# schaltplan.net
KiCad netlist of a schematic drawn in EAGLE
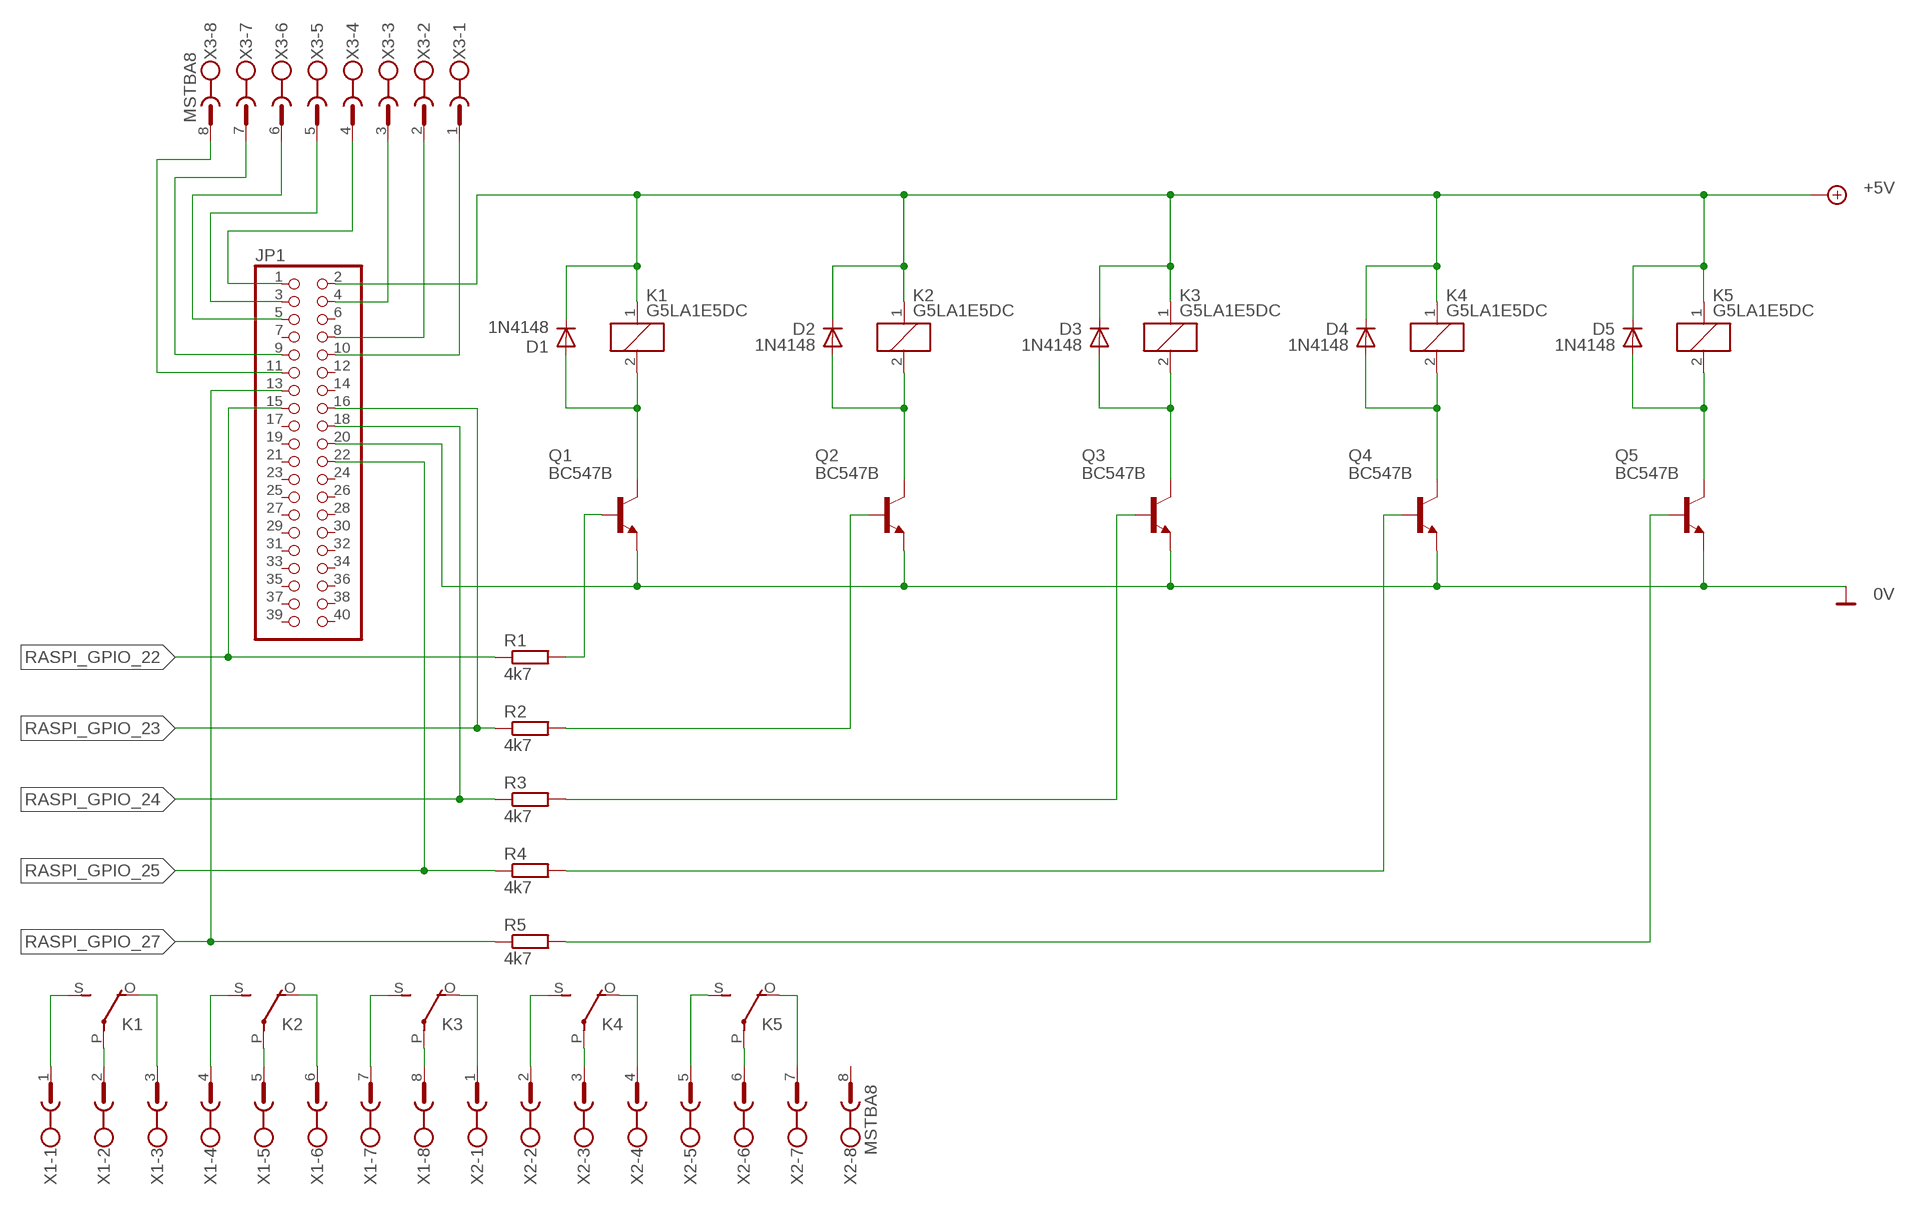
[diagram p0: schematic, sheet 1]

(export (version "E")
  (design (tool "Eeschema 10.0.6"))
  (components
    (comp (ref "D1")
      (value "1N4148")
      (footprint "eagle-import:DO35-10")
      (libsource (lib "eagle-import") (part "1N4148DO35-10"))
    )
    (comp (ref "D2")
      (value "1N4148")
      (footprint "eagle-import:DO35-10")
      (libsource (lib "eagle-import") (part "1N4148DO35-10"))
    )
    (comp (ref "D3")
      (value "1N4148")
      (footprint "eagle-import:DO35-10")
      (libsource (lib "eagle-import") (part "1N4148DO35-10"))
    )
    (comp (ref "D4")
      (value "1N4148")
      (footprint "eagle-import:DO35-10")
      (libsource (lib "eagle-import") (part "1N4148DO35-10"))
    )
    (comp (ref "D5")
      (value "1N4148")
      (footprint "eagle-import:DO35-10")
      (libsource (lib "eagle-import") (part "1N4148DO35-10"))
    )
    (comp (ref "JP1")
      (value "PINHD-2X20")
      (footprint "eagle-import:2X20")
      (libsource (lib "eagle-import") (part "PINHD-2X20"))
    )
    (comp (ref "K1")
      (value "G5LA1E5DC")
      (footprint "eagle-import:G5LE")
      (libsource (lib "eagle-import") (part "G5L"))
    )
    (comp (ref "K2")
      (value "G5LA1E5DC")
      (footprint "eagle-import:G5LE")
      (libsource (lib "eagle-import") (part "G5L"))
    )
    (comp (ref "K3")
      (value "G5LA1E5DC")
      (footprint "eagle-import:G5LE")
      (libsource (lib "eagle-import") (part "G5L"))
    )
    (comp (ref "K4")
      (value "G5LA1E5DC")
      (footprint "eagle-import:G5LE")
      (libsource (lib "eagle-import") (part "G5L"))
    )
    (comp (ref "K5")
      (value "G5LA1E5DC")
      (footprint "eagle-import:G5LE")
      (libsource (lib "eagle-import") (part "G5L"))
    )
    (comp (ref "Q1")
      (value "BC547B")
      (footprint "eagle-import:TO92")
      (libsource (lib "eagle-import") (part "BC547B"))
    )
    (comp (ref "Q2")
      (value "BC547B")
      (footprint "eagle-import:TO92")
      (libsource (lib "eagle-import") (part "BC547B"))
    )
    (comp (ref "Q3")
      (value "BC547B")
      (footprint "eagle-import:TO92")
      (libsource (lib "eagle-import") (part "BC547B"))
    )
    (comp (ref "Q4")
      (value "BC547B")
      (footprint "eagle-import:TO92")
      (libsource (lib "eagle-import") (part "BC547B"))
    )
    (comp (ref "Q5")
      (value "BC547B")
      (footprint "eagle-import:TO92")
      (libsource (lib "eagle-import") (part "BC547B"))
    )
    (comp (ref "R1")
      (value "4k7")
      (footprint "eagle-import:0207_10")
      (libsource (lib "eagle-import") (part "R-EU_0207/10"))
    )
    (comp (ref "R2")
      (value "4k7")
      (footprint "eagle-import:0207_10")
      (libsource (lib "eagle-import") (part "R-EU_0207/10"))
    )
    (comp (ref "R3")
      (value "4k7")
      (footprint "eagle-import:0207_10")
      (libsource (lib "eagle-import") (part "R-EU_0207/10"))
    )
    (comp (ref "R4")
      (value "4k7")
      (footprint "eagle-import:0207_10")
      (libsource (lib "eagle-import") (part "R-EU_0207/10"))
    )
    (comp (ref "R5")
      (value "4k7")
      (footprint "eagle-import:0207_10")
      (libsource (lib "eagle-import") (part "R-EU_0207/10"))
    )
    (comp (ref "X1")
      (value "MSTBA8")
      (footprint "eagle-import:MSTBA8")
      (fields (field (name "MF") "FARNELL") (field (name "MPN") "1757307"))
      (libsource (lib "eagle-import") (part "MSTBA8"))
    )
    (comp (ref "X2")
      (value "MSTBA8")
      (footprint "eagle-import:MSTBA8")
      (fields (field (name "MF") "FARNELL") (field (name "MPN") "1757307"))
      (libsource (lib "eagle-import") (part "MSTBA8"))
    )
    (comp (ref "X3")
      (value "MSTBA8")
      (footprint "eagle-import:MSTBA8")
      (fields (field (name "MF") "FARNELL") (field (name "MPN") "1757307"))
      (libsource (lib "eagle-import") (part "MSTBA8"))
    )
  )
  (nets
    (net (code "1") (name "+5V") (class "Default")
      (node (ref "D1") (pin "C") (pinfunction "C_C") (pintype "passive"))
      (node (ref "D2") (pin "C") (pinfunction "C_C") (pintype "passive"))
      (node (ref "D3") (pin "C") (pinfunction "C_C") (pintype "passive"))
      (node (ref "D4") (pin "C") (pinfunction "C_C") (pintype "passive"))
      (node (ref "D5") (pin "C") (pinfunction "C_C") (pintype "passive"))
      (node (ref "JP1") (pin "2") (pinfunction "2_2") (pintype "passive"))
      (node (ref "K1") (pin "1") (pinfunction "1_1") (pintype "passive"))
      (node (ref "K2") (pin "1") (pinfunction "1_1") (pintype "passive"))
      (node (ref "K3") (pin "1") (pinfunction "1_1") (pintype "passive"))
      (node (ref "K4") (pin "1") (pinfunction "1_1") (pintype "passive"))
      (node (ref "K5") (pin "1") (pinfunction "1_1") (pintype "passive"))
    )
    (net (code "2") (name "0V") (class "Default")
      (node (ref "JP1") (pin "20") (pinfunction "20_20") (pintype "passive"))
      (node (ref "Q1") (pin "1") (pinfunction "E_1") (pintype "passive"))
      (node (ref "Q2") (pin "1") (pinfunction "E_1") (pintype "passive"))
      (node (ref "Q3") (pin "1") (pinfunction "E_1") (pintype "passive"))
      (node (ref "Q4") (pin "1") (pinfunction "E_1") (pintype "passive"))
      (node (ref "Q5") (pin "1") (pinfunction "E_1") (pintype "passive"))
    )
    (net (code "3") (name "Net-(JP1-Pad10)") (class "Default")
      (node (ref "JP1") (pin "10") (pinfunction "10_10") (pintype "passive"))
      (node (ref "X3") (pin "1") (pinfunction "1_1") (pintype "passive"))
    )
    (net (code "4") (name "Net-(K1-PadS)") (class "Default")
      (node (ref "K1") (pin "S") (pinfunction "S_S") (pintype "passive"))
      (node (ref "X1") (pin "1") (pinfunction "1_1") (pintype "passive"))
    )
    (net (code "5") (name "Net-(K3-PadO)") (class "Default")
      (node (ref "K3") (pin "O") (pinfunction "O_O") (pintype "passive"))
      (node (ref "X2") (pin "1") (pinfunction "1_1") (pintype "passive"))
    )
    (net (code "6") (name "Net-(Q1-B)") (class "Default")
      (node (ref "Q1") (pin "2") (pinfunction "B_2") (pintype "passive"))
      (node (ref "R1") (pin "2") (pinfunction "2_2") (pintype "passive"))
    )
    (net (code "7") (name "Net-(Q1-C)") (class "Default")
      (node (ref "D1") (pin "A") (pinfunction "A_A") (pintype "passive"))
      (node (ref "K1") (pin "2") (pinfunction "2_2") (pintype "passive"))
      (node (ref "Q1") (pin "3") (pinfunction "C_3") (pintype "passive"))
    )
    (net (code "8") (name "Net-(Q2-B)") (class "Default")
      (node (ref "Q2") (pin "2") (pinfunction "B_2") (pintype "passive"))
      (node (ref "R2") (pin "2") (pinfunction "2_2") (pintype "passive"))
    )
    (net (code "9") (name "Net-(Q2-C)") (class "Default")
      (node (ref "D2") (pin "A") (pinfunction "A_A") (pintype "passive"))
      (node (ref "K2") (pin "2") (pinfunction "2_2") (pintype "passive"))
      (node (ref "Q2") (pin "3") (pinfunction "C_3") (pintype "passive"))
    )
    (net (code "10") (name "Net-(Q3-B)") (class "Default")
      (node (ref "Q3") (pin "2") (pinfunction "B_2") (pintype "passive"))
      (node (ref "R3") (pin "2") (pinfunction "2_2") (pintype "passive"))
    )
    (net (code "11") (name "Net-(Q3-C)") (class "Default")
      (node (ref "D3") (pin "A") (pinfunction "A_A") (pintype "passive"))
      (node (ref "K3") (pin "2") (pinfunction "2_2") (pintype "passive"))
      (node (ref "Q3") (pin "3") (pinfunction "C_3") (pintype "passive"))
    )
    (net (code "12") (name "Net-(Q4-B)") (class "Default")
      (node (ref "Q4") (pin "2") (pinfunction "B_2") (pintype "passive"))
      (node (ref "R4") (pin "2") (pinfunction "2_2") (pintype "passive"))
    )
    (net (code "13") (name "Net-(Q4-C)") (class "Default")
      (node (ref "D4") (pin "A") (pinfunction "A_A") (pintype "passive"))
      (node (ref "K4") (pin "2") (pinfunction "2_2") (pintype "passive"))
      (node (ref "Q4") (pin "3") (pinfunction "C_3") (pintype "passive"))
    )
    (net (code "14") (name "Net-(Q5-B)") (class "Default")
      (node (ref "Q5") (pin "2") (pinfunction "B_2") (pintype "passive"))
      (node (ref "R5") (pin "2") (pinfunction "2_2") (pintype "passive"))
    )
    (net (code "15") (name "Net-(Q5-C)") (class "Default")
      (node (ref "D5") (pin "A") (pinfunction "A_A") (pintype "passive"))
      (node (ref "K5") (pin "2") (pinfunction "2_2") (pintype "passive"))
      (node (ref "Q5") (pin "3") (pinfunction "C_3") (pintype "passive"))
    )
    (net (code "16") (name "Net-(X1B-1)") (class "Default")
      (node (ref "K1") (pin "P") (pinfunction "P_P") (pintype "passive"))
      (node (ref "X1") (pin "2") (pinfunction "1_2") (pintype "passive"))
    )
    (net (code "17") (name "Net-(X1C-1)") (class "Default")
      (node (ref "K1") (pin "O") (pinfunction "O_O") (pintype "passive"))
      (node (ref "X1") (pin "3") (pinfunction "1_3") (pintype "passive"))
    )
    (net (code "18") (name "Net-(X1D-1)") (class "Default")
      (node (ref "K2") (pin "S") (pinfunction "S_S") (pintype "passive"))
      (node (ref "X1") (pin "4") (pinfunction "1_4") (pintype "passive"))
    )
    (net (code "19") (name "Net-(X1E-1)") (class "Default")
      (node (ref "K2") (pin "P") (pinfunction "P_P") (pintype "passive"))
      (node (ref "X1") (pin "5") (pinfunction "1_5") (pintype "passive"))
    )
    (net (code "20") (name "Net-(X1F-1)") (class "Default")
      (node (ref "K2") (pin "O") (pinfunction "O_O") (pintype "passive"))
      (node (ref "X1") (pin "6") (pinfunction "1_6") (pintype "passive"))
    )
    (net (code "21") (name "Net-(X1G-1)") (class "Default")
      (node (ref "K3") (pin "S") (pinfunction "S_S") (pintype "passive"))
      (node (ref "X1") (pin "7") (pinfunction "1_7") (pintype "passive"))
    )
    (net (code "22") (name "Net-(X1H-1)") (class "Default")
      (node (ref "K3") (pin "P") (pinfunction "P_P") (pintype "passive"))
      (node (ref "X1") (pin "8") (pinfunction "1_8") (pintype "passive"))
    )
    (net (code "23") (name "Net-(X2B-1)") (class "Default")
      (node (ref "K4") (pin "S") (pinfunction "S_S") (pintype "passive"))
      (node (ref "X2") (pin "2") (pinfunction "1_2") (pintype "passive"))
    )
    (net (code "24") (name "Net-(X2C-1)") (class "Default")
      (node (ref "K4") (pin "P") (pinfunction "P_P") (pintype "passive"))
      (node (ref "X2") (pin "3") (pinfunction "1_3") (pintype "passive"))
    )
    (net (code "25") (name "Net-(X2D-1)") (class "Default")
      (node (ref "K4") (pin "O") (pinfunction "O_O") (pintype "passive"))
      (node (ref "X2") (pin "4") (pinfunction "1_4") (pintype "passive"))
    )
    (net (code "26") (name "Net-(X2E-1)") (class "Default")
      (node (ref "K5") (pin "S") (pinfunction "S_S") (pintype "passive"))
      (node (ref "X2") (pin "5") (pinfunction "1_5") (pintype "passive"))
    )
    (net (code "27") (name "Net-(X2F-1)") (class "Default")
      (node (ref "K5") (pin "P") (pinfunction "P_P") (pintype "passive"))
      (node (ref "X2") (pin "6") (pinfunction "1_6") (pintype "passive"))
    )
    (net (code "28") (name "Net-(X2G-1)") (class "Default")
      (node (ref "K5") (pin "O") (pinfunction "O_O") (pintype "passive"))
      (node (ref "X2") (pin "7") (pinfunction "1_7") (pintype "passive"))
    )
    (net (code "29") (name "Net-(X3B-1)") (class "Default")
      (node (ref "JP1") (pin "8") (pinfunction "8_8") (pintype "passive"))
      (node (ref "X3") (pin "2") (pinfunction "1_2") (pintype "passive"))
    )
    (net (code "30") (name "Net-(X3C-1)") (class "Default")
      (node (ref "JP1") (pin "4") (pinfunction "4_4") (pintype "passive"))
      (node (ref "X3") (pin "3") (pinfunction "1_3") (pintype "passive"))
    )
    (net (code "31") (name "Net-(X3D-1)") (class "Default")
      (node (ref "JP1") (pin "1") (pinfunction "1_1") (pintype "passive"))
      (node (ref "X3") (pin "4") (pinfunction "1_4") (pintype "passive"))
    )
    (net (code "32") (name "Net-(X3E-1)") (class "Default")
      (node (ref "JP1") (pin "3") (pinfunction "3_3") (pintype "passive"))
      (node (ref "X3") (pin "5") (pinfunction "1_5") (pintype "passive"))
    )
    (net (code "33") (name "Net-(X3F-1)") (class "Default")
      (node (ref "JP1") (pin "5") (pinfunction "5_5") (pintype "passive"))
      (node (ref "X3") (pin "6") (pinfunction "1_6") (pintype "passive"))
    )
    (net (code "34") (name "Net-(X3G-1)") (class "Default")
      (node (ref "JP1") (pin "9") (pinfunction "9_9") (pintype "passive"))
      (node (ref "X3") (pin "7") (pinfunction "1_7") (pintype "passive"))
    )
    (net (code "35") (name "Net-(X3H-1)") (class "Default")
      (node (ref "JP1") (pin "11") (pinfunction "11_11") (pintype "passive"))
      (node (ref "X3") (pin "8") (pinfunction "1_8") (pintype "passive"))
    )
    (net (code "36") (name "RASPI_GPIO_22") (class "Default")
      (node (ref "JP1") (pin "15") (pinfunction "15_15") (pintype "passive"))
      (node (ref "R1") (pin "1") (pinfunction "1_1") (pintype "passive"))
    )
    (net (code "37") (name "RASPI_GPIO_23") (class "Default")
      (node (ref "JP1") (pin "16") (pinfunction "16_16") (pintype "passive"))
      (node (ref "R2") (pin "1") (pinfunction "1_1") (pintype "passive"))
    )
    (net (code "38") (name "RASPI_GPIO_24") (class "Default")
      (node (ref "JP1") (pin "18") (pinfunction "18_18") (pintype "passive"))
      (node (ref "R3") (pin "1") (pinfunction "1_1") (pintype "passive"))
    )
    (net (code "39") (name "RASPI_GPIO_25") (class "Default")
      (node (ref "JP1") (pin "22") (pinfunction "22_22") (pintype "passive"))
      (node (ref "R4") (pin "1") (pinfunction "1_1") (pintype "passive"))
    )
    (net (code "40") (name "RASPI_GPIO_27") (class "Default")
      (node (ref "JP1") (pin "13") (pinfunction "13_13") (pintype "passive"))
      (node (ref "R5") (pin "1") (pinfunction "1_1") (pintype "passive"))
    )
    (net (code "41") (name "unconnected-(JP1-Pad6)") (class "Default")
      (node (ref "JP1") (pin "6") (pinfunction "6_6") (pintype "passive"))
    )
    (net (code "42") (name "unconnected-(JP1-Pad7)") (class "Default")
      (node (ref "JP1") (pin "7") (pinfunction "7_7") (pintype "passive"))
    )
    (net (code "43") (name "unconnected-(JP1-Pad12)") (class "Default")
      (node (ref "JP1") (pin "12") (pinfunction "12_12") (pintype "passive"))
    )
    (net (code "44") (name "unconnected-(JP1-Pad14)") (class "Default")
      (node (ref "JP1") (pin "14") (pinfunction "14_14") (pintype "passive"))
    )
    (net (code "45") (name "unconnected-(JP1-Pad17)") (class "Default")
      (node (ref "JP1") (pin "17") (pinfunction "17_17") (pintype "passive"))
    )
    (net (code "46") (name "unconnected-(JP1-Pad19)") (class "Default")
      (node (ref "JP1") (pin "19") (pinfunction "19_19") (pintype "passive"))
    )
    (net (code "47") (name "unconnected-(JP1-Pad21)") (class "Default")
      (node (ref "JP1") (pin "21") (pinfunction "21_21") (pintype "passive"))
    )
    (net (code "48") (name "unconnected-(JP1-Pad23)") (class "Default")
      (node (ref "JP1") (pin "23") (pinfunction "23_23") (pintype "passive"))
    )
    (net (code "49") (name "unconnected-(JP1-Pad24)") (class "Default")
      (node (ref "JP1") (pin "24") (pinfunction "24_24") (pintype "passive"))
    )
    (net (code "50") (name "unconnected-(JP1-Pad25)") (class "Default")
      (node (ref "JP1") (pin "25") (pinfunction "25_25") (pintype "passive"))
    )
    (net (code "51") (name "unconnected-(JP1-Pad26)") (class "Default")
      (node (ref "JP1") (pin "26") (pinfunction "26_26") (pintype "passive"))
    )
    (net (code "52") (name "unconnected-(JP1-Pad27)") (class "Default")
      (node (ref "JP1") (pin "27") (pinfunction "27_27") (pintype "passive"))
    )
    (net (code "53") (name "unconnected-(JP1-Pad28)") (class "Default")
      (node (ref "JP1") (pin "28") (pinfunction "28_28") (pintype "passive"))
    )
    (net (code "54") (name "unconnected-(JP1-Pad29)") (class "Default")
      (node (ref "JP1") (pin "29") (pinfunction "29_29") (pintype "passive"))
    )
    (net (code "55") (name "unconnected-(JP1-Pad30)") (class "Default")
      (node (ref "JP1") (pin "30") (pinfunction "30_30") (pintype "passive"))
    )
    (net (code "56") (name "unconnected-(JP1-Pad31)") (class "Default")
      (node (ref "JP1") (pin "31") (pinfunction "31_31") (pintype "passive"))
    )
    (net (code "57") (name "unconnected-(JP1-Pad32)") (class "Default")
      (node (ref "JP1") (pin "32") (pinfunction "32_32") (pintype "passive"))
    )
    (net (code "58") (name "unconnected-(JP1-Pad33)") (class "Default")
      (node (ref "JP1") (pin "33") (pinfunction "33_33") (pintype "passive"))
    )
    (net (code "59") (name "unconnected-(JP1-Pad34)") (class "Default")
      (node (ref "JP1") (pin "34") (pinfunction "34_34") (pintype "passive"))
    )
    (net (code "60") (name "unconnected-(JP1-Pad35)") (class "Default")
      (node (ref "JP1") (pin "35") (pinfunction "35_35") (pintype "passive"))
    )
    (net (code "61") (name "unconnected-(JP1-Pad36)") (class "Default")
      (node (ref "JP1") (pin "36") (pinfunction "36_36") (pintype "passive"))
    )
    (net (code "62") (name "unconnected-(JP1-Pad37)") (class "Default")
      (node (ref "JP1") (pin "37") (pinfunction "37_37") (pintype "passive"))
    )
    (net (code "63") (name "unconnected-(JP1-Pad38)") (class "Default")
      (node (ref "JP1") (pin "38") (pinfunction "38_38") (pintype "passive"))
    )
    (net (code "64") (name "unconnected-(JP1-Pad39)") (class "Default")
      (node (ref "JP1") (pin "39") (pinfunction "39_39") (pintype "passive"))
    )
    (net (code "65") (name "unconnected-(JP1-Pad40)") (class "Default")
      (node (ref "JP1") (pin "40") (pinfunction "40_40") (pintype "passive"))
    )
    (net (code "66") (name "unconnected-(X2H-1-Pad8)") (class "Default")
      (node (ref "X2") (pin "8") (pinfunction "1_8") (pintype "passive"))
    )
  )
)
